# 00A-051.net
KiCad netlist of a schematic drawn in EAGLE
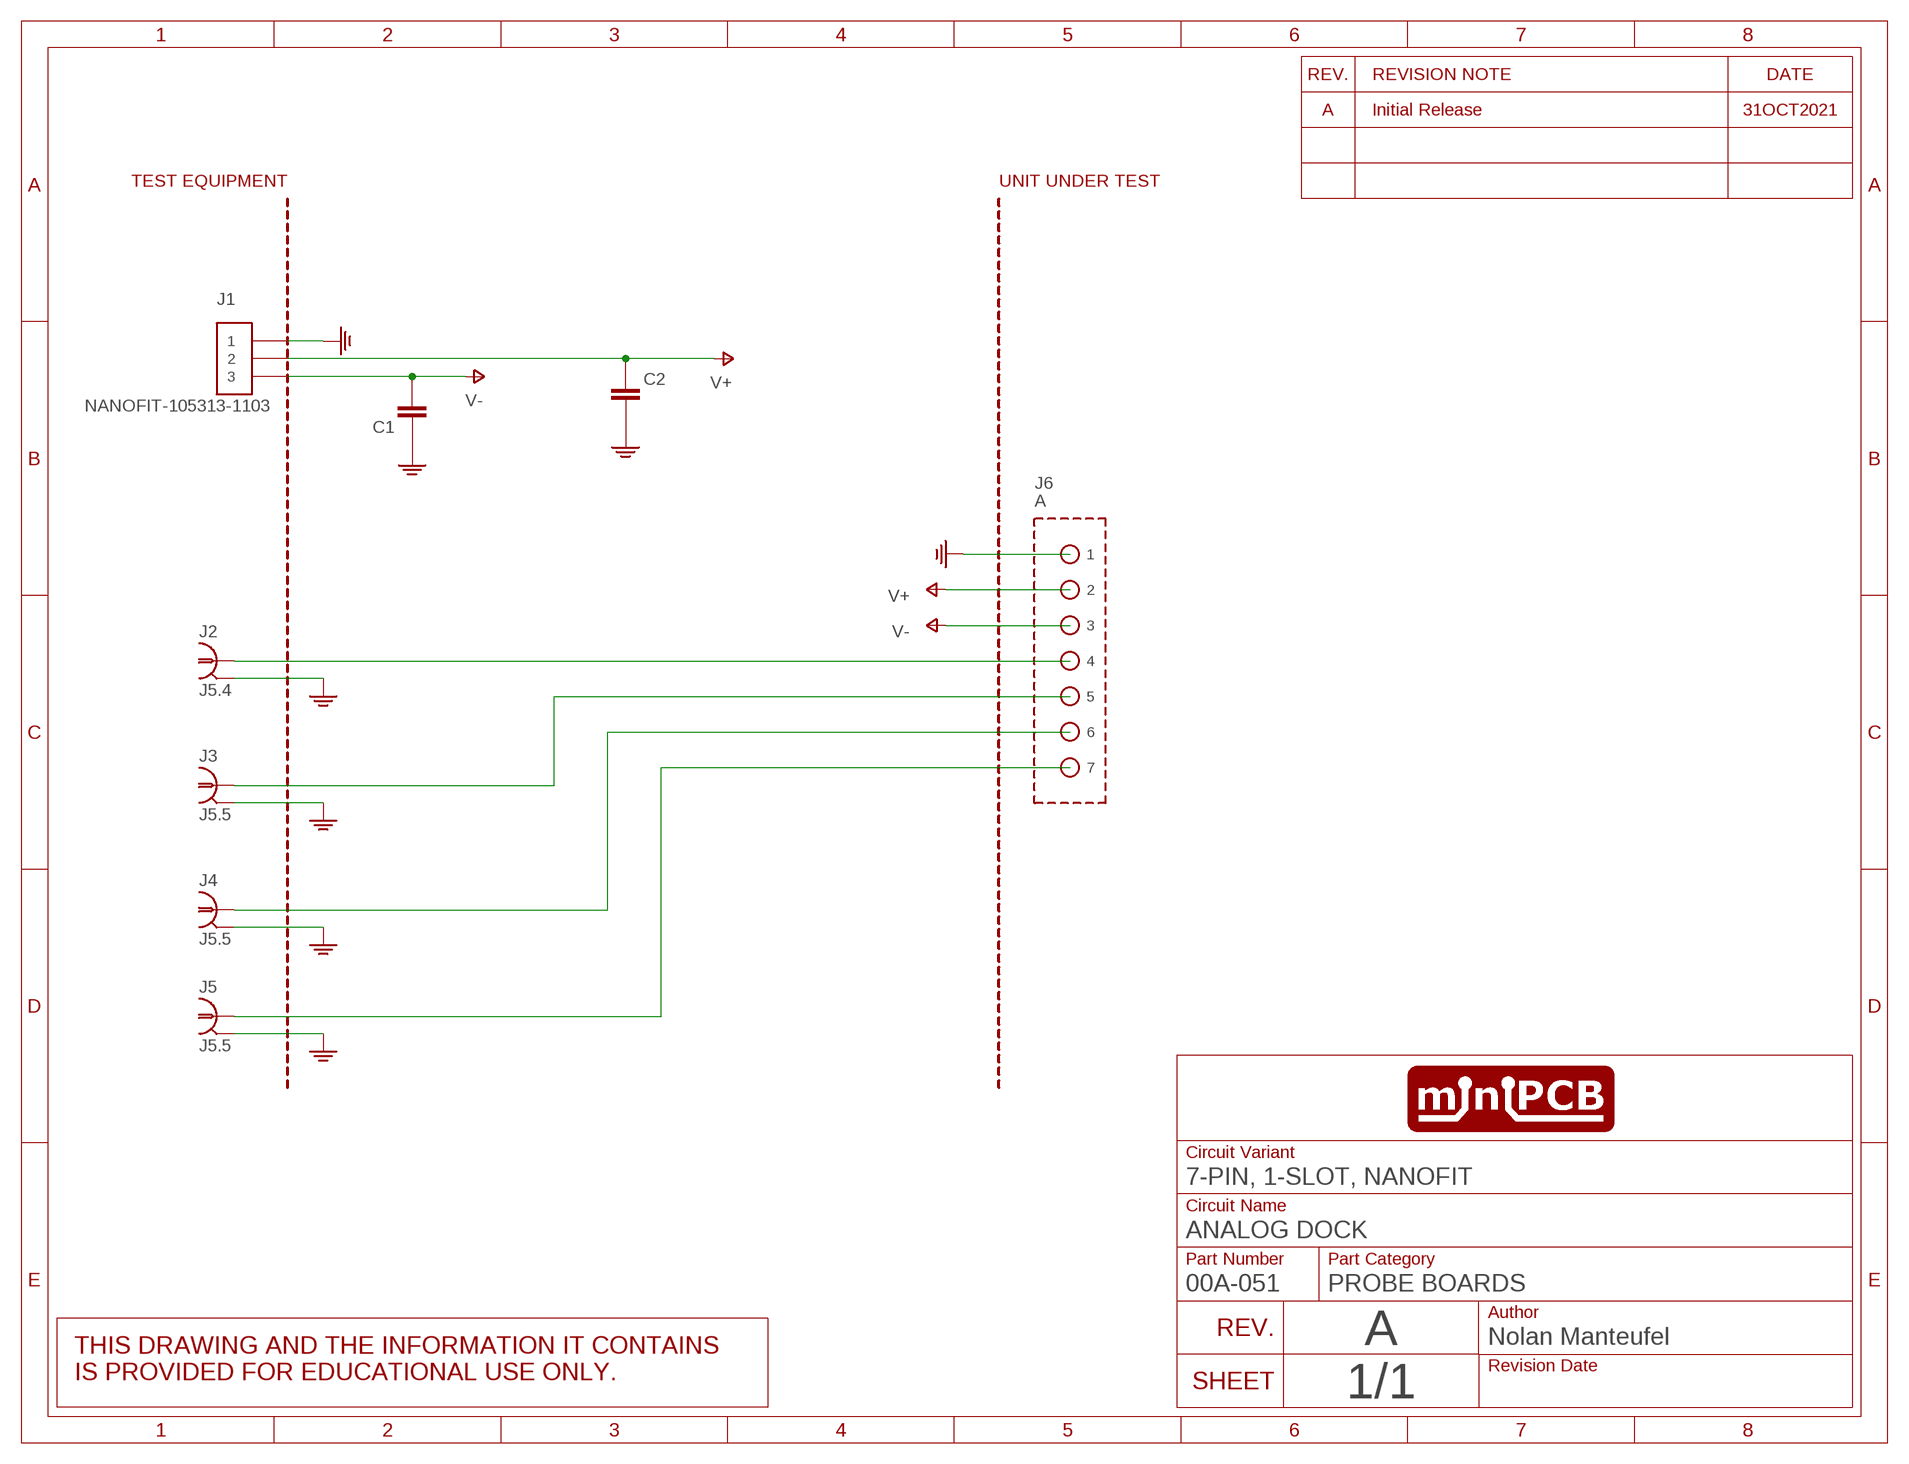
[diagram p0: schematic, sheet 1]

(export (version "E")
  (design (tool "Eeschema 10.0.6"))
  (components
    (comp (ref "C1")
      (value "CAPACITOR_10")
      (footprint "eagle-import:C5MM")
      (libsource (lib "eagle-import") (part "CAPACITOR_10"))
    )
    (comp (ref "C2")
      (value "CAPACITOR_10")
      (footprint "eagle-import:C5MM")
      (libsource (lib "eagle-import") (part "CAPACITOR_10"))
    )
    (comp (ref "J1")
      (value "NANOFIT-105313-1103")
      (footprint "eagle-import:PINS_3-NANOFIT-H")
      (libsource (lib "eagle-import") (part "PINS_3-NANOFIT-105313-1103"))
    )
    (comp (ref "J2")
      (value "J5.4")
      (footprint "eagle-import:B35N14H")
      (libsource (lib "eagle-import") (part "BNC_35N14"))
    )
    (comp (ref "J3")
      (value "J5.5")
      (footprint "eagle-import:B35N14H")
      (libsource (lib "eagle-import") (part "BNC_35N14"))
    )
    (comp (ref "J4")
      (value "J5.5")
      (footprint "eagle-import:B35N14H")
      (libsource (lib "eagle-import") (part "BNC_35N14"))
    )
    (comp (ref "J5")
      (value "J5.5")
      (footprint "eagle-import:B35N14H")
      (libsource (lib "eagle-import") (part "BNC_35N14"))
    )
    (comp (ref "J6")
      (value "A")
      (footprint "eagle-import:MINIPCB_DOCK_7P")
      (fields (field (name "SLOT") "A"))
      (libsource (lib "eagle-import") (part "MINIPCB_DOCK_7P"))
    )
    (comp (ref "PCB")
      (value "MINIPCB_0PDOCK_50X100")
      (footprint "eagle-import:MINIPCB_DOCK_50X100")
      (fields (field (name "PART_NUMBER") "00A-051"))
      (libsource (lib "eagle-import") (part "MINIPCB_0PDOCK_50X100"))
    )
  )
  (nets
    (net (code "1") (name "GND") (class "Default")
      (node (ref "C1") (pin "+") (pinfunction "+_+") (pintype "passive"))
      (node (ref "C2") (pin "-") (pinfunction "-_-") (pintype "passive"))
      (node (ref "J1") (pin "1") (pinfunction "1_1") (pintype "bidirectional"))
      (node (ref "J2") (pin "2.GND") (pinfunction "GND_2.GND") (pintype "power_in"))
      (node (ref "J2") (pin "3.GND") (pinfunction "GND_3.GND") (pintype "power_in"))
      (node (ref "J2") (pin "4.GND") (pinfunction "GND_4.GND") (pintype "power_in"))
      (node (ref "J2") (pin "5.GND") (pinfunction "GND_5.GND") (pintype "power_in"))
      (node (ref "J3") (pin "2.GND") (pinfunction "GND_2.GND") (pintype "power_in"))
      (node (ref "J3") (pin "3.GND") (pinfunction "GND_3.GND") (pintype "power_in"))
      (node (ref "J3") (pin "4.GND") (pinfunction "GND_4.GND") (pintype "power_in"))
      (node (ref "J3") (pin "5.GND") (pinfunction "GND_5.GND") (pintype "power_in"))
      (node (ref "J4") (pin "2.GND") (pinfunction "GND_2.GND") (pintype "power_in"))
      (node (ref "J4") (pin "3.GND") (pinfunction "GND_3.GND") (pintype "power_in"))
      (node (ref "J4") (pin "4.GND") (pinfunction "GND_4.GND") (pintype "power_in"))
      (node (ref "J4") (pin "5.GND") (pinfunction "GND_5.GND") (pintype "power_in"))
      (node (ref "J5") (pin "2.GND") (pinfunction "GND_2.GND") (pintype "power_in"))
      (node (ref "J5") (pin "3.GND") (pinfunction "GND_3.GND") (pintype "power_in"))
      (node (ref "J5") (pin "4.GND") (pinfunction "GND_4.GND") (pintype "power_in"))
      (node (ref "J5") (pin "5.GND") (pinfunction "GND_5.GND") (pintype "power_in"))
      (node (ref "J6") (pin "1") (pinfunction "1_1") (pintype "bidirectional"))
    )
    (net (code "2") (name "Net-(J2-1)") (class "Default")
      (node (ref "J2") (pin "1.SIG") (pinfunction "1_1.SIG") (pintype "passive"))
      (node (ref "J6") (pin "4") (pinfunction "4_4") (pintype "bidirectional"))
    )
    (net (code "3") (name "Net-(J3-1)") (class "Default")
      (node (ref "J3") (pin "1.SIG") (pinfunction "1_1.SIG") (pintype "passive"))
      (node (ref "J6") (pin "5") (pinfunction "5_5") (pintype "bidirectional"))
    )
    (net (code "4") (name "Net-(J4-1)") (class "Default")
      (node (ref "J4") (pin "1.SIG") (pinfunction "1_1.SIG") (pintype "passive"))
      (node (ref "J6") (pin "6") (pinfunction "6_6") (pintype "bidirectional"))
    )
    (net (code "5") (name "Net-(J5-1)") (class "Default")
      (node (ref "J5") (pin "1.SIG") (pinfunction "1_1.SIG") (pintype "passive"))
      (node (ref "J6") (pin "7") (pinfunction "7_7") (pintype "bidirectional"))
    )
    (net (code "6") (name "V+") (class "Default")
      (node (ref "C2") (pin "+") (pinfunction "+_+") (pintype "passive"))
      (node (ref "J1") (pin "2") (pinfunction "2_2") (pintype "bidirectional"))
      (node (ref "J6") (pin "2") (pinfunction "2_2") (pintype "bidirectional"))
    )
    (net (code "7") (name "V-") (class "Default")
      (node (ref "C1") (pin "-") (pinfunction "-_-") (pintype "passive"))
      (node (ref "J1") (pin "3") (pinfunction "3_3") (pintype "bidirectional"))
      (node (ref "J6") (pin "3") (pinfunction "3_3") (pintype "bidirectional"))
    )
  )
)
